# AUX_CurrentSource.net
KiCad netlist of a schematic drawn in Altium Designer
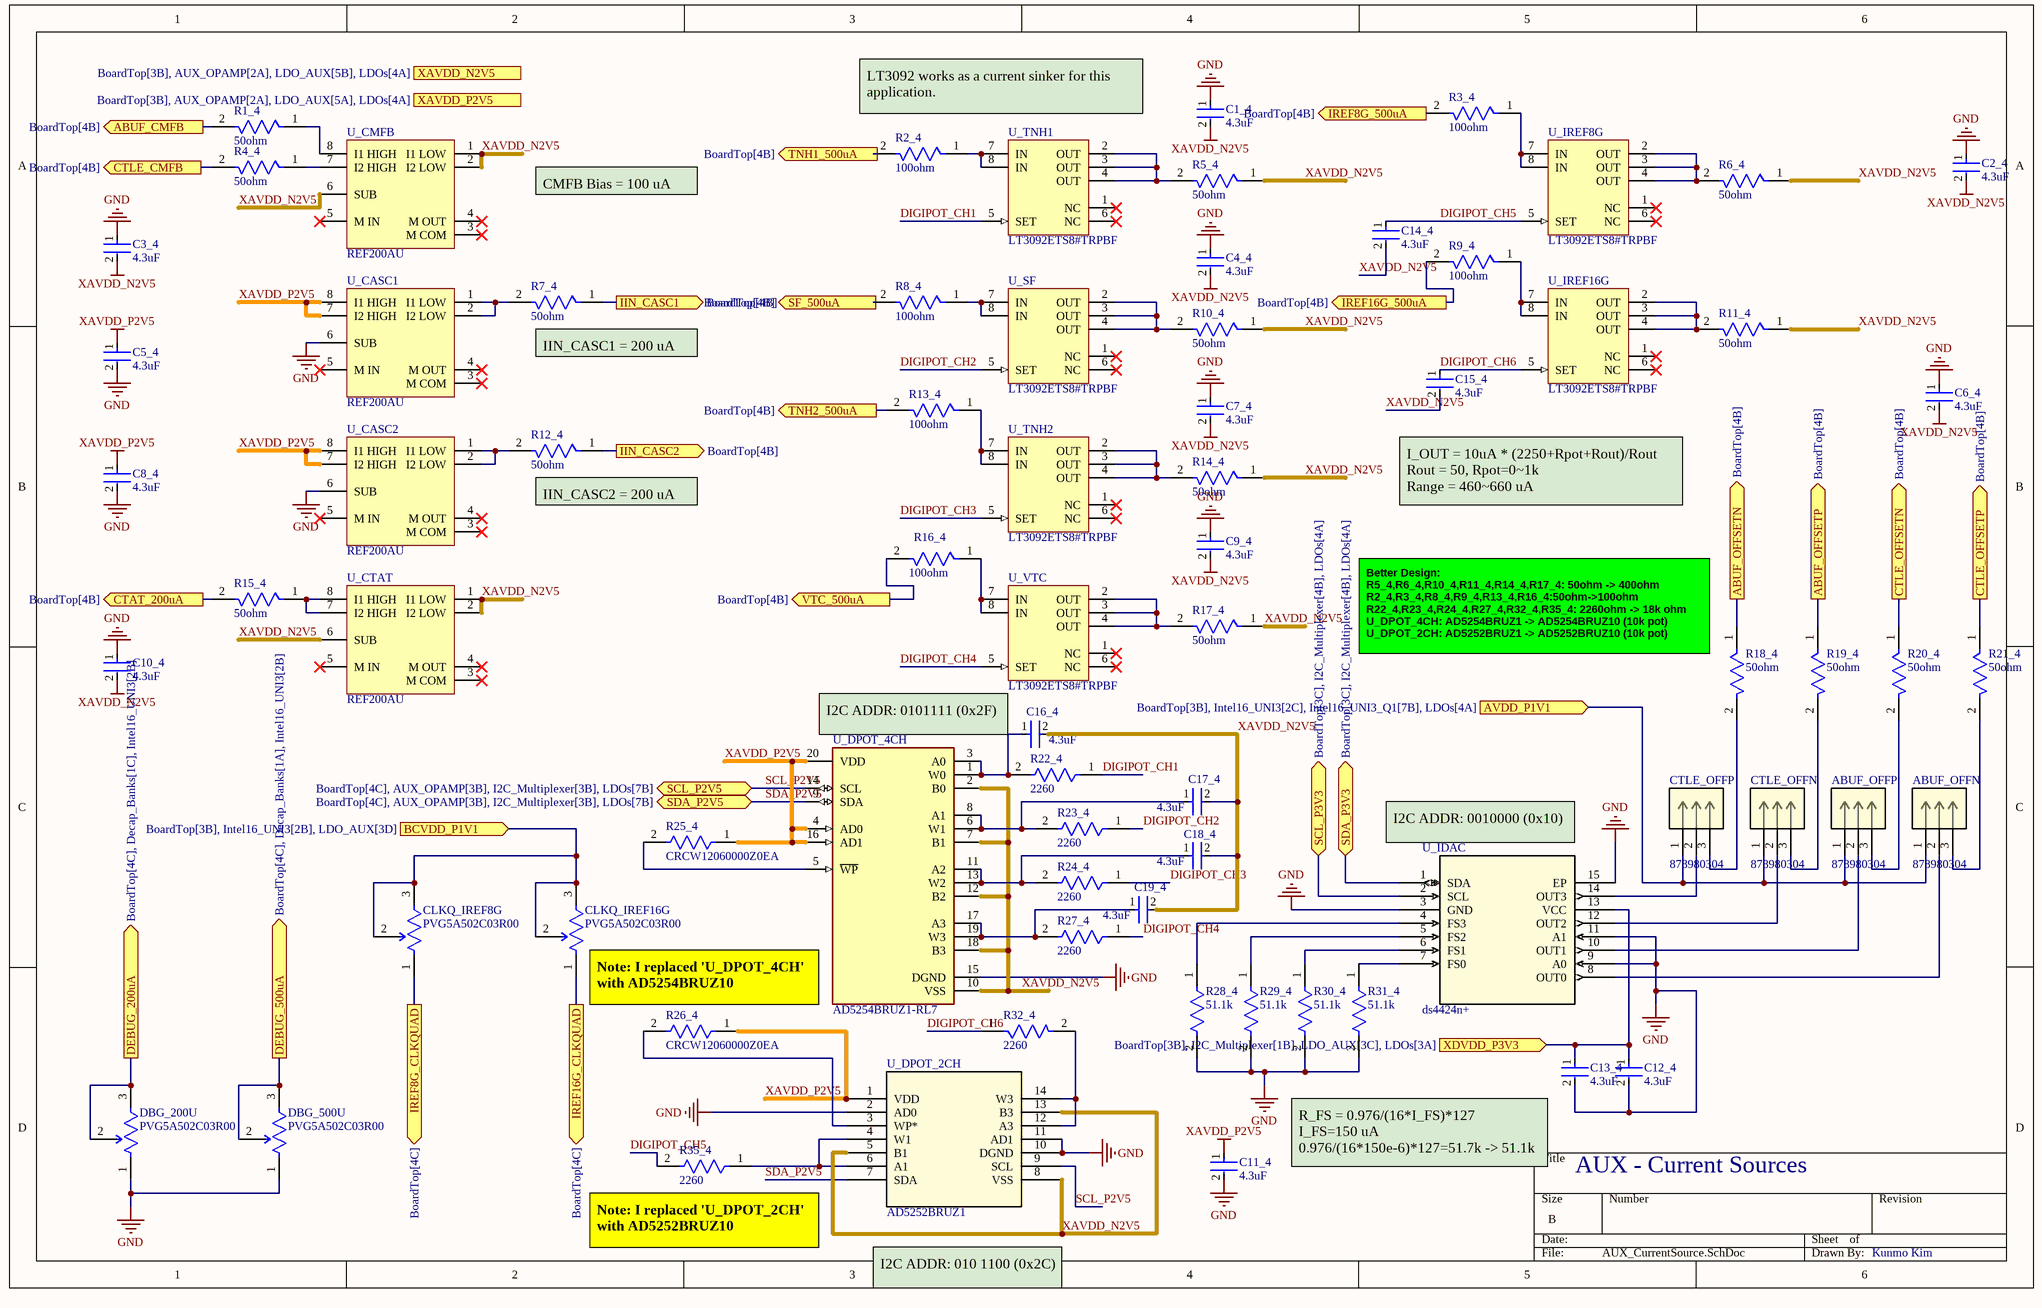
[diagram p0: AUX_CurrentSource.SchDoc]

(export (version "E")
  (design (tool "Eeschema 10.0.6"))
  (components
    (comp (ref "ABUF_OFFN")
      (value "878980304")
      (footprint "CONN03_87898_M-5p84_MOL")
      (description "No Description Available")
      (libsource (lib "878980304") (part "878980304"))
    )
    (comp (ref "ABUF_OFFP")
      (value "878980304")
      (footprint "CONN03_87898_M-5p84_MOL")
      (description "No Description Available")
      (libsource (lib "878980304") (part "878980304"))
    )
    (comp (ref "C1_4")
      (value "4.3uF")
      (footprint "FP-LLL1U4-0_05-MFG")
      (description "Cap Ceramic Monolithic 4.3uF 20% 4V X5R 15% 02404 (0610M)")
      (fields (field (name "TOLERANCE") "20%"))
      (libsource (lib "LLL_cap") (part "CMP-06035-061933-1"))
    )
    (comp (ref "C2_4")
      (value "4.3uF")
      (footprint "FP-LLL1U4-0_05-MFG")
      (description "Cap Ceramic Monolithic 4.3uF 20% 4V X5R 15% 02404 (0610M)")
      (fields (field (name "TOLERANCE") "20%"))
      (libsource (lib "LLL_cap") (part "CMP-06035-061933-1"))
    )
    (comp (ref "C3_4")
      (value "4.3uF")
      (footprint "FP-LLL1U4-0_05-MFG")
      (description "Cap Ceramic Monolithic 4.3uF 20% 4V X5R 15% 02404 (0610M)")
      (fields (field (name "TOLERANCE") "20%"))
      (libsource (lib "LLL_cap") (part "CMP-06035-061933-1"))
    )
    (comp (ref "C4_4")
      (value "4.3uF")
      (footprint "FP-LLL1U4-0_05-MFG")
      (description "Cap Ceramic Monolithic 4.3uF 20% 4V X5R 15% 02404 (0610M)")
      (fields (field (name "TOLERANCE") "20%"))
      (libsource (lib "LLL_cap") (part "CMP-06035-061933-1"))
    )
    (comp (ref "C5_4")
      (value "4.3uF")
      (footprint "FP-LLL1U4-0_05-MFG")
      (description "Cap Ceramic Monolithic 4.3uF 20% 4V X5R 15% 02404 (0610M)")
      (fields (field (name "TOLERANCE") "20%"))
      (libsource (lib "LLL_cap") (part "CMP-06035-061933-1"))
    )
    (comp (ref "C6_4")
      (value "4.3uF")
      (footprint "FP-LLL1U4-0_05-MFG")
      (description "Cap Ceramic Monolithic 4.3uF 20% 4V X5R 15% 02404 (0610M)")
      (fields (field (name "TOLERANCE") "20%"))
      (libsource (lib "LLL_cap") (part "CMP-06035-061933-1"))
    )
    (comp (ref "C7_4")
      (value "4.3uF")
      (footprint "FP-LLL1U4-0_05-MFG")
      (description "Cap Ceramic Monolithic 4.3uF 20% 4V X5R 15% 02404 (0610M)")
      (fields (field (name "TOLERANCE") "20%"))
      (libsource (lib "LLL_cap") (part "CMP-06035-061933-1"))
    )
    (comp (ref "C8_4")
      (value "4.3uF")
      (footprint "FP-LLL1U4-0_05-MFG")
      (description "Cap Ceramic Monolithic 4.3uF 20% 4V X5R 15% 02404 (0610M)")
      (fields (field (name "TOLERANCE") "20%"))
      (libsource (lib "LLL_cap") (part "CMP-06035-061933-1"))
    )
    (comp (ref "C9_4")
      (value "4.3uF")
      (footprint "FP-LLL1U4-0_05-MFG")
      (description "Cap Ceramic Monolithic 4.3uF 20% 4V X5R 15% 02404 (0610M)")
      (fields (field (name "TOLERANCE") "20%"))
      (libsource (lib "LLL_cap") (part "CMP-06035-061933-1"))
    )
    (comp (ref "C10_4")
      (value "4.3uF")
      (footprint "FP-LLL1U4-0_05-MFG")
      (description "Cap Ceramic Monolithic 4.3uF 20% 4V X5R 15% 02404 (0610M)")
      (fields (field (name "TOLERANCE") "20%"))
      (libsource (lib "LLL_cap") (part "CMP-06035-061933-1"))
    )
    (comp (ref "C11_4")
      (value "4.3uF")
      (footprint "FP-LLL1U4-0_05-MFG")
      (description "Cap Ceramic Monolithic 4.3uF 20% 4V X5R 15% 02404 (0610M)")
      (fields (field (name "TOLERANCE") "20%"))
      (libsource (lib "LLL_cap") (part "CMP-06035-061933-1"))
    )
    (comp (ref "C12_4")
      (value "4.3uF")
      (footprint "FP-LLL1U4-0_05-MFG")
      (description "Cap Ceramic Monolithic 4.3uF 20% 4V X5R 15% 02404 (0610M)")
      (fields (field (name "TOLERANCE") "20%"))
      (libsource (lib "LLL_cap") (part "CMP-06035-061933-1"))
    )
    (comp (ref "C13_4")
      (value "4.3uF")
      (footprint "FP-LLL1U4-0_05-MFG")
      (description "Cap Ceramic Monolithic 4.3uF 20% 4V X5R 15% 02404 (0610M)")
      (fields (field (name "TOLERANCE") "20%"))
      (libsource (lib "LLL_cap") (part "CMP-06035-061933-1"))
    )
    (comp (ref "C14_4")
      (value "4.3uF")
      (footprint "FP-LLL1U4-0_05-MFG")
      (description "Cap Ceramic Monolithic 4.3uF 20% 4V X5R 15% 02404 (0610M)")
      (fields (field (name "TOLERANCE") "20%"))
      (libsource (lib "LLL_cap") (part "CMP-06035-061933-1"))
    )
    (comp (ref "C15_4")
      (value "4.3uF")
      (footprint "FP-LLL1U4-0_05-MFG")
      (description "Cap Ceramic Monolithic 4.3uF 20% 4V X5R 15% 02404 (0610M)")
      (fields (field (name "TOLERANCE") "20%"))
      (libsource (lib "LLL_cap") (part "CMP-06035-061933-1"))
    )
    (comp (ref "C16_4")
      (value "4.3uF")
      (footprint "FP-LLL1U4-0_05-MFG")
      (description "Cap Ceramic Monolithic 4.3uF 20% 4V X5R 15% 02404 (0610M)")
      (fields (field (name "TOLERANCE") "20%"))
      (libsource (lib "LLL_cap") (part "CMP-06035-061933-1"))
    )
    (comp (ref "C17_4")
      (value "4.3uF")
      (footprint "FP-LLL1U4-0_05-MFG")
      (description "Cap Ceramic Monolithic 4.3uF 20% 4V X5R 15% 02404 (0610M)")
      (fields (field (name "TOLERANCE") "20%"))
      (libsource (lib "LLL_cap") (part "CMP-06035-061933-1"))
    )
    (comp (ref "C18_4")
      (value "4.3uF")
      (footprint "FP-LLL1U4-0_05-MFG")
      (description "Cap Ceramic Monolithic 4.3uF 20% 4V X5R 15% 02404 (0610M)")
      (fields (field (name "TOLERANCE") "20%"))
      (libsource (lib "LLL_cap") (part "CMP-06035-061933-1"))
    )
    (comp (ref "C19_4")
      (value "4.3uF")
      (footprint "FP-LLL1U4-0_05-MFG")
      (description "Cap Ceramic Monolithic 4.3uF 20% 4V X5R 15% 02404 (0610M)")
      (fields (field (name "TOLERANCE") "20%"))
      (libsource (lib "LLL_cap") (part "CMP-06035-061933-1"))
    )
    (comp (ref "CLKQ_IREF8G")
      (value "PVG5A502C03R00")
      (footprint "FP-PVG5A-MFG")
      (description "PVG5A502C03R00 Resistor Trimmer, Cermet, 5 kOhm, ± 10%, 250 mW, 12 Turn, Multi Turn, Surface Mount")
      (fields (field (name "TOLERANCE") "10%"))
      (libsource (lib "PVG5A502C03R00") (part "CMP-00059-71526922-1"))
    )
    (comp (ref "CLKQ_IREF16G")
      (value "PVG5A502C03R00")
      (footprint "FP-PVG5A-MFG")
      (description "PVG5A502C03R00 Resistor Trimmer, Cermet, 5 kOhm, ± 10%, 250 mW, 12 Turn, Multi Turn, Surface Mount")
      (fields (field (name "TOLERANCE") "10%"))
      (libsource (lib "PVG5A502C03R00") (part "CMP-00059-71526922-1"))
    )
    (comp (ref "CTLE_OFFN")
      (value "878980304")
      (footprint "CONN03_87898_M-5p84_MOL")
      (description "No Description Available")
      (libsource (lib "878980304") (part "878980304"))
    )
    (comp (ref "CTLE_OFFP")
      (value "878980304")
      (footprint "CONN03_87898_M-5p84_MOL")
      (description "No Description Available")
      (libsource (lib "878980304") (part "878980304"))
    )
    (comp (ref "DBG_200U")
      (value "PVG5A502C03R00")
      (footprint "FP-PVG5A-MFG")
      (description "PVG5A502C03R00 Resistor Trimmer, Cermet, 5 kOhm, ± 10%, 250 mW, 12 Turn, Multi Turn, Surface Mount")
      (fields (field (name "TOLERANCE") "10%"))
      (libsource (lib "PVG5A502C03R00") (part "CMP-00059-71526922-1"))
    )
    (comp (ref "DBG_500U")
      (value "PVG5A502C03R00")
      (footprint "FP-PVG5A-MFG")
      (description "PVG5A502C03R00 Resistor Trimmer, Cermet, 5 kOhm, ± 10%, 250 mW, 12 Turn, Multi Turn, Surface Mount")
      (fields (field (name "TOLERANCE") "10%"))
      (libsource (lib "PVG5A502C03R00") (part "CMP-00059-71526922-1"))
    )
    (comp (ref "R1_4")
      (value "50ohm")
      (footprint "FP-RT0402-0_35-IPC_A")
      (fields (field (name "TOLERANCE") "0.1%"))
      (libsource (lib "resistor_50ohm_0402_0p1ptol") (part "1029c3af85768c4190bb7ad29bc67b5"))
    )
    (comp (ref "R2_4")
      (value "100ohm")
      (footprint "FP-RT0402-0_35-IPC_A")
      (fields (field (name "TOLERANCE") "0.1%"))
      (libsource (lib "resistor_50ohm_0402_0p1ptol") (part "1029c3af85768c4190bb7ad29bc67b5"))
    )
    (comp (ref "R3_4")
      (value "100ohm")
      (footprint "FP-RT0402-0_35-IPC_A")
      (fields (field (name "TOLERANCE") "0.1%"))
      (libsource (lib "resistor_50ohm_0402_0p1ptol") (part "1029c3af85768c4190bb7ad29bc67b5"))
    )
    (comp (ref "R4_4")
      (value "50ohm")
      (footprint "FP-RT0402-0_35-IPC_A")
      (fields (field (name "TOLERANCE") "0.1%"))
      (libsource (lib "resistor_50ohm_0402_0p1ptol") (part "1029c3af85768c4190bb7ad29bc67b5"))
    )
    (comp (ref "R5_4")
      (value "50ohm")
      (footprint "FP-RT0402-0_35-IPC_A")
      (fields (field (name "TOLERANCE") "0.1%"))
      (libsource (lib "resistor_50ohm_0402_0p1ptol") (part "1029c3af85768c4190bb7ad29bc67b5"))
    )
    (comp (ref "R6_4")
      (value "50ohm")
      (footprint "FP-RT0402-0_35-IPC_A")
      (fields (field (name "TOLERANCE") "0.1%"))
      (libsource (lib "resistor_50ohm_0402_0p1ptol") (part "1029c3af85768c4190bb7ad29bc67b5"))
    )
    (comp (ref "R7_4")
      (value "50ohm")
      (footprint "FP-RT0402-0_35-IPC_A")
      (fields (field (name "TOLERANCE") "0.1%"))
      (libsource (lib "resistor_50ohm_0402_0p1ptol") (part "1029c3af85768c4190bb7ad29bc67b5"))
    )
    (comp (ref "R8_4")
      (value "100ohm")
      (footprint "FP-RT0402-0_35-IPC_A")
      (fields (field (name "TOLERANCE") "0.1%"))
      (libsource (lib "resistor_50ohm_0402_0p1ptol") (part "1029c3af85768c4190bb7ad29bc67b5"))
    )
    (comp (ref "R9_4")
      (value "100ohm")
      (footprint "FP-RT0402-0_35-IPC_A")
      (fields (field (name "TOLERANCE") "0.1%"))
      (libsource (lib "resistor_50ohm_0402_0p1ptol") (part "1029c3af85768c4190bb7ad29bc67b5"))
    )
    (comp (ref "R10_4")
      (value "50ohm")
      (footprint "FP-RT0402-0_35-IPC_A")
      (fields (field (name "TOLERANCE") "0.1%"))
      (libsource (lib "resistor_50ohm_0402_0p1ptol") (part "1029c3af85768c4190bb7ad29bc67b5"))
    )
    (comp (ref "R11_4")
      (value "50ohm")
      (footprint "FP-RT0402-0_35-IPC_A")
      (fields (field (name "TOLERANCE") "0.1%"))
      (libsource (lib "resistor_50ohm_0402_0p1ptol") (part "1029c3af85768c4190bb7ad29bc67b5"))
    )
    (comp (ref "R12_4")
      (value "50ohm")
      (footprint "FP-RT0402-0_35-IPC_A")
      (fields (field (name "TOLERANCE") "0.1%"))
      (libsource (lib "resistor_50ohm_0402_0p1ptol") (part "1029c3af85768c4190bb7ad29bc67b5"))
    )
    (comp (ref "R13_4")
      (value "100ohm")
      (footprint "FP-RT0402-0_35-IPC_A")
      (fields (field (name "TOLERANCE") "0.1%"))
      (libsource (lib "resistor_50ohm_0402_0p1ptol") (part "1029c3af85768c4190bb7ad29bc67b5"))
    )
    (comp (ref "R14_4")
      (value "50ohm")
      (footprint "FP-RT0402-0_35-IPC_A")
      (fields (field (name "TOLERANCE") "0.1%"))
      (libsource (lib "resistor_50ohm_0402_0p1ptol") (part "1029c3af85768c4190bb7ad29bc67b5"))
    )
    (comp (ref "R15_4")
      (value "50ohm")
      (footprint "FP-RT0402-0_35-IPC_A")
      (fields (field (name "TOLERANCE") "0.1%"))
      (libsource (lib "resistor_50ohm_0402_0p1ptol") (part "1029c3af85768c4190bb7ad29bc67b5"))
    )
    (comp (ref "R16_4")
      (value "100ohm")
      (footprint "FP-RT0402-0_35-IPC_A")
      (fields (field (name "TOLERANCE") "0.1%"))
      (libsource (lib "resistor_50ohm_0402_0p1ptol") (part "1029c3af85768c4190bb7ad29bc67b5"))
    )
    (comp (ref "R17_4")
      (value "50ohm")
      (footprint "FP-RT0402-0_35-IPC_A")
      (fields (field (name "TOLERANCE") "0.1%"))
      (libsource (lib "resistor_50ohm_0402_0p1ptol") (part "1029c3af85768c4190bb7ad29bc67b5"))
    )
    (comp (ref "R18_4")
      (value "50ohm")
      (footprint "FP-RT0402-0_35-IPC_A")
      (fields (field (name "TOLERANCE") "0.1%"))
      (libsource (lib "resistor_50ohm_0402_0p1ptol") (part "1029c3af85768c4190bb7ad29bc67b5"))
    )
    (comp (ref "R19_4")
      (value "50ohm")
      (footprint "FP-RT0402-0_35-IPC_A")
      (fields (field (name "TOLERANCE") "0.1%"))
      (libsource (lib "resistor_50ohm_0402_0p1ptol") (part "1029c3af85768c4190bb7ad29bc67b5"))
    )
    (comp (ref "R20_4")
      (value "50ohm")
      (footprint "FP-RT0402-0_35-IPC_A")
      (fields (field (name "TOLERANCE") "0.1%"))
      (libsource (lib "resistor_50ohm_0402_0p1ptol") (part "1029c3af85768c4190bb7ad29bc67b5"))
    )
    (comp (ref "R21_4")
      (value "50ohm")
      (footprint "FP-RT0402-0_35-IPC_A")
      (fields (field (name "TOLERANCE") "0.1%"))
      (libsource (lib "resistor_50ohm_0402_0p1ptol") (part "1029c3af85768c4190bb7ad29bc67b5"))
    )
    (comp (ref "R22_4")
      (value "2260")
      (footprint "FP-RG1005-MFG")
      (description "Automotive Metal Thin Film Chip Resistor, 0402, 2.26kΩ, 0.1%, 25ppm/°C, 0.0625W, 75V")
      (fields (field (name "TOLERANCE") "0.1%"))
      (libsource (lib "Altium Content Vault") (part "1029c3af85768c4190bb7ad29bc67b5"))
    )
    (comp (ref "R23_4")
      (value "2260")
      (footprint "FP-RG1005-MFG")
      (description "Automotive Metal Thin Film Chip Resistor, 0402, 2.26kΩ, 0.1%, 25ppm/°C, 0.0625W, 75V")
      (fields (field (name "TOLERANCE") "0.1%"))
      (libsource (lib "Altium Content Vault") (part "1029c3af85768c4190bb7ad29bc67b5"))
    )
    (comp (ref "R24_4")
      (value "2260")
      (footprint "FP-RG1005-MFG")
      (description "Automotive Metal Thin Film Chip Resistor, 0402, 2.26kΩ, 0.1%, 25ppm/°C, 0.0625W, 75V")
      (fields (field (name "TOLERANCE") "0.1%"))
      (libsource (lib "Altium Content Vault") (part "1029c3af85768c4190bb7ad29bc67b5"))
    )
    (comp (ref "R25_4")
      (value "CRCW12060000Z0EA")
      (footprint "FP-CRCW1206-e3-IPC_C")
      (description "RES Thick Film, 0Ω, 0.25W, 1206")
      (fields (field (name "TOLERANCE") "1%"))
      (libsource (lib "Altium Content Vault") (part "1029c3af85768c4190bb7ad29bc67b5"))
    )
    (comp (ref "R26_4")
      (value "CRCW12060000Z0EA")
      (footprint "FP-CRCW1206-e3-IPC_C")
      (description "RES Thick Film, 0Ω, 0.25W, 1206")
      (fields (field (name "TOLERANCE") "1%"))
      (libsource (lib "Altium Content Vault") (part "1029c3af85768c4190bb7ad29bc67b5"))
    )
    (comp (ref "R27_4")
      (value "2260")
      (footprint "FP-RG1005-MFG")
      (description "Automotive Metal Thin Film Chip Resistor, 0402, 2.26kΩ, 0.1%, 25ppm/°C, 0.0625W, 75V")
      (fields (field (name "TOLERANCE") "0.1%"))
      (libsource (lib "Altium Content Vault") (part "1029c3af85768c4190bb7ad29bc67b5"))
    )
    (comp (ref "R28_4")
      (value "51.1k")
      (footprint "FP-RT0603-MFG")
      (description "RES SMD 51.1K OHM 0.1% 1/10W")
      (fields (field (name "MANUFACTURER") "Yageo") (field (name "TOLERANCE") "0.001"))
      (libsource (lib "Altium Content Vault") (part "1029c3af85768c4190bb7ad29bc67b5"))
    )
    (comp (ref "R29_4")
      (value "51.1k")
      (footprint "FP-RT0603-MFG")
      (description "RES SMD 51.1K OHM 0.1% 1/10W")
      (fields (field (name "MANUFACTURER") "Yageo") (field (name "TOLERANCE") "0.001"))
      (libsource (lib "Altium Content Vault") (part "1029c3af85768c4190bb7ad29bc67b5"))
    )
    (comp (ref "R30_4")
      (value "51.1k")
      (footprint "FP-RT0603-MFG")
      (description "RES SMD 51.1K OHM 0.1% 1/10W")
      (fields (field (name "MANUFACTURER") "Yageo") (field (name "TOLERANCE") "0.001"))
      (libsource (lib "Altium Content Vault") (part "1029c3af85768c4190bb7ad29bc67b5"))
    )
    (comp (ref "R31_4")
      (value "51.1k")
      (footprint "FP-RT0603-MFG")
      (description "RES SMD 51.1K OHM 0.1% 1/10W")
      (fields (field (name "MANUFACTURER") "Yageo") (field (name "TOLERANCE") "0.001"))
      (libsource (lib "Altium Content Vault") (part "1029c3af85768c4190bb7ad29bc67b5"))
    )
    (comp (ref "R32_4")
      (value "2260")
      (footprint "FP-RG1005-MFG")
      (description "Automotive Metal Thin Film Chip Resistor, 0402, 2.26kΩ, 0.1%, 25ppm/°C, 0.0625W, 75V")
      (fields (field (name "TOLERANCE") "0.1%"))
      (libsource (lib "Altium Content Vault") (part "1029c3af85768c4190bb7ad29bc67b5"))
    )
    (comp (ref "R35_4")
      (value "2260")
      (footprint "FP-RG1005-MFG")
      (description "Automotive Metal Thin Film Chip Resistor, 0402, 2.26kΩ, 0.1%, 25ppm/°C, 0.0625W, 75V")
      (fields (field (name "TOLERANCE") "0.1%"))
      (libsource (lib "Altium Content Vault") (part "1029c3af85768c4190bb7ad29bc67b5"))
    )
    (comp (ref "U_CASC1")
      (value "REF200AU")
      (footprint "D0008A_N")
      (fields (field (name "MANUFACTURER") "Texas Instruments"))
      (libsource (lib "REF200") (part "CMP-0368-00004-2"))
    )
    (comp (ref "U_CASC2")
      (value "REF200AU")
      (footprint "D0008A_N")
      (fields (field (name "MANUFACTURER") "Texas Instruments"))
      (libsource (lib "REF200") (part "CMP-0368-00004-2"))
    )
    (comp (ref "U_CMFB")
      (value "REF200AU")
      (footprint "D0008A_N")
      (fields (field (name "MANUFACTURER") "Texas Instruments"))
      (libsource (lib "REF200") (part "CMP-0368-00004-2"))
    )
    (comp (ref "U_CTAT")
      (value "REF200AU")
      (footprint "D0008A_N")
      (fields (field (name "MANUFACTURER") "Texas Instruments"))
      (libsource (lib "REF200") (part "CMP-0368-00004-2"))
    )
    (comp (ref "U_DPOT_2CH")
      (value "AD5252BRUZ1")
      (footprint "RU_14_ADI")
      (description "No Description Available")
      (libsource (lib "AD5252BRUZ1") (part "AD5252BRUZ1"))
    )
    (comp (ref "U_DPOT_4CH")
      (value "AD5254BRUZ1-RL7")
      (footprint "FP-RU-20-IPC_B")
      (description "IC DGTL POT 1KOHM 256TAP 20TSSOP")
      (fields (field (name "TOLERANCE") "30%"))
      (libsource (lib "AD5254_1k") (part "CMP-09083-000143-1"))
    )
    (comp (ref "U_IDAC")
      (value "ds4424n+")
      (footprint "21-0137_T1433+2_MXM")
      (description "No Description Available")
      (libsource (lib "ds4424n&plus_") (part "ds4424n+"))
    )
    (comp (ref "U_IREF8G")
      (value "LT3092ETS8#TRPBF")
      (footprint "TSOT-23_TS8")
      (fields (field (name "MANUFACTURER") "Linear Technology"))
      (libsource (lib "LT3092") (part "CMP-0472-00072-1"))
    )
    (comp (ref "U_IREF16G")
      (value "LT3092ETS8#TRPBF")
      (footprint "TSOT-23_TS8")
      (fields (field (name "MANUFACTURER") "Linear Technology"))
      (libsource (lib "LT3092") (part "CMP-0472-00072-1"))
    )
    (comp (ref "U_SF")
      (value "LT3092ETS8#TRPBF")
      (footprint "TSOT-23_TS8")
      (fields (field (name "MANUFACTURER") "Linear Technology"))
      (libsource (lib "LT3092") (part "CMP-0472-00072-1"))
    )
    (comp (ref "U_TNH1")
      (value "LT3092ETS8#TRPBF")
      (footprint "TSOT-23_TS8")
      (fields (field (name "MANUFACTURER") "Linear Technology"))
      (libsource (lib "LT3092") (part "CMP-0472-00072-1"))
    )
    (comp (ref "U_TNH2")
      (value "LT3092ETS8#TRPBF")
      (footprint "TSOT-23_TS8")
      (fields (field (name "MANUFACTURER") "Linear Technology"))
      (libsource (lib "LT3092") (part "CMP-0472-00072-1"))
    )
    (comp (ref "U_VTC")
      (value "LT3092ETS8#TRPBF")
      (footprint "TSOT-23_TS8")
      (fields (field (name "MANUFACTURER") "Linear Technology"))
      (libsource (lib "LT3092") (part "CMP-0472-00072-1"))
    )
  )
  (nets
    (net (code "2") (name "/ABUF_CMFB") (class "Default")
      (node (ref "R1_4") (pin "2") (pinfunction "2_2") (pintype "passive"))
    )
    (net (code "3") (name "/ABUF_OFFSETN") (class "Default")
      (node (ref "R18_4") (pin "1") (pinfunction "1_1") (pintype "passive"))
    )
    (net (code "4") (name "/ABUF_OFFSETP") (class "Default")
      (node (ref "R19_4") (pin "1") (pinfunction "1_1") (pintype "passive"))
    )
    (net (code "5") (name "/AVDD_P1V1") (class "Default")
      (node (ref "ABUF_OFFN") (pin "1") (pinfunction "1_1") (pintype "passive"))
      (node (ref "ABUF_OFFP") (pin "1") (pinfunction "1_1") (pintype "passive"))
      (node (ref "CTLE_OFFN") (pin "1") (pinfunction "1_1") (pintype "passive"))
      (node (ref "CTLE_OFFP") (pin "1") (pinfunction "1_1") (pintype "passive"))
    )
    (net (code "6") (name "/BCVDD_P1V1") (class "Default")
      (node (ref "CLKQ_IREF16G") (pin "2") (pinfunction "WIPER_2") (pintype "passive"))
      (node (ref "CLKQ_IREF16G") (pin "3") (pinfunction "CW_3") (pintype "passive"))
      (node (ref "CLKQ_IREF8G") (pin "2") (pinfunction "WIPER_2") (pintype "passive"))
      (node (ref "CLKQ_IREF8G") (pin "3") (pinfunction "CW_3") (pintype "passive"))
    )
    (net (code "7") (name "/CTAT_200uA") (class "Default")
      (node (ref "R15_4") (pin "2") (pinfunction "2_2") (pintype "passive"))
    )
    (net (code "8") (name "/CTLE_CMFB") (class "Default")
      (node (ref "R4_4") (pin "2") (pinfunction "2_2") (pintype "passive"))
    )
    (net (code "9") (name "/CTLE_OFFSETN") (class "Default")
      (node (ref "R20_4") (pin "1") (pinfunction "1_1") (pintype "passive"))
    )
    (net (code "10") (name "/CTLE_OFFSETP") (class "Default")
      (node (ref "R21_4") (pin "1") (pinfunction "1_1") (pintype "passive"))
    )
    (net (code "11") (name "/DEBUG_200uA") (class "Default")
      (node (ref "DBG_200U") (pin "2") (pinfunction "WIPER_2") (pintype "passive"))
      (node (ref "DBG_200U") (pin "3") (pinfunction "CW_3") (pintype "passive"))
    )
    (net (code "12") (name "/DEBUG_500uA") (class "Default")
      (node (ref "DBG_500U") (pin "2") (pinfunction "WIPER_2") (pintype "passive"))
      (node (ref "DBG_500U") (pin "3") (pinfunction "CW_3") (pintype "passive"))
    )
    (net (code "13") (name "/DIGIPOT_CH1") (class "Default")
      (node (ref "R22_4") (pin "1") (pinfunction "1_1") (pintype "passive"))
      (node (ref "U_TNH1") (pin "5") (pinfunction "SET_5") (pintype "input"))
    )
    (net (code "14") (name "/DIGIPOT_CH2") (class "Default")
      (node (ref "R23_4") (pin "1") (pinfunction "1_1") (pintype "passive"))
      (node (ref "U_SF") (pin "5") (pinfunction "SET_5") (pintype "input"))
    )
    (net (code "15") (name "/DIGIPOT_CH3") (class "Default")
      (node (ref "R24_4") (pin "1") (pinfunction "1_1") (pintype "passive"))
      (node (ref "U_TNH2") (pin "5") (pinfunction "SET_5") (pintype "input"))
    )
    (net (code "16") (name "/DIGIPOT_CH4") (class "Default")
      (node (ref "R27_4") (pin "1") (pinfunction "1_1") (pintype "passive"))
      (node (ref "U_VTC") (pin "5") (pinfunction "SET_5") (pintype "input"))
    )
    (net (code "17") (name "/DIGIPOT_CH5") (class "Default")
      (node (ref "C14_4") (pin "1") (pinfunction "1_1") (pintype "passive"))
      (node (ref "R35_4") (pin "2") (pinfunction "2_2") (pintype "passive"))
      (node (ref "U_IREF8G") (pin "5") (pinfunction "SET_5") (pintype "input"))
    )
    (net (code "18") (name "/DIGIPOT_CH6") (class "Default")
      (node (ref "C15_4") (pin "1") (pinfunction "1_1") (pintype "passive"))
      (node (ref "R32_4") (pin "1") (pinfunction "1_1") (pintype "passive"))
      (node (ref "U_IREF16G") (pin "5") (pinfunction "SET_5") (pintype "input"))
    )
    (net (code "19") (name "/IIN_CASC1") (class "Default")
      (node (ref "R7_4") (pin "1") (pinfunction "1_1") (pintype "passive"))
    )
    (net (code "20") (name "/IIN_CASC2") (class "Default")
      (node (ref "R12_4") (pin "1") (pinfunction "1_1") (pintype "passive"))
    )
    (net (code "21") (name "/IREF8G_500uA") (class "Default")
      (node (ref "R3_4") (pin "2") (pinfunction "2_2") (pintype "passive"))
    )
    (net (code "22") (name "/IREF8G_CLKQUAD") (class "Default")
      (node (ref "CLKQ_IREF8G") (pin "1") (pinfunction "CCW_1") (pintype "passive"))
    )
    (net (code "23") (name "/IREF16G_500uA") (class "Default")
      (node (ref "R9_4") (pin "2") (pinfunction "2_2") (pintype "passive"))
    )
    (net (code "24") (name "/IREF16G_CLKQUAD") (class "Default")
      (node (ref "CLKQ_IREF16G") (pin "1") (pinfunction "CCW_1") (pintype "passive"))
    )
    (net (code "25") (name "/SCL_P2V5") (class "Default")
      (node (ref "U_DPOT_2CH") (pin "9") (pinfunction "SCL_9") (pintype "passive"))
      (node (ref "U_DPOT_4CH") (pin "14") (pinfunction "SCL_14") (pintype "bidirectional"))
    )
    (net (code "26") (name "/SCL_P3V3") (class "Default")
      (node (ref "U_IDAC") (pin "2") (pinfunction "SCL_2") (pintype "input"))
    )
    (net (code "27") (name "/SDA_P2V5") (class "Default")
      (node (ref "U_DPOT_2CH") (pin "7") (pinfunction "SDA_7") (pintype "passive"))
      (node (ref "U_DPOT_4CH") (pin "9") (pinfunction "SDA_9") (pintype "bidirectional"))
    )
    (net (code "28") (name "/SDA_P3V3") (class "Default")
      (node (ref "U_IDAC") (pin "1") (pinfunction "SDA_1") (pintype "bidirectional"))
    )
    (net (code "29") (name "/SF_500uA") (class "Default")
      (node (ref "R8_4") (pin "2") (pinfunction "2_2") (pintype "passive"))
    )
    (net (code "30") (name "/TNH1_500uA") (class "Default")
      (node (ref "R2_4") (pin "2") (pinfunction "2_2") (pintype "passive"))
    )
    (net (code "31") (name "/TNH2_500uA") (class "Default")
      (node (ref "R13_4") (pin "2") (pinfunction "2_2") (pintype "passive"))
    )
    (net (code "32") (name "/VTC_500uA") (class "Default")
      (node (ref "R16_4") (pin "2") (pinfunction "2_2") (pintype "passive"))
    )
    (net (code "33") (name "/XDVDD_P3V3") (class "Default")
      (node (ref "C12_4") (pin "1") (pinfunction "1_1") (pintype "passive"))
      (node (ref "C13_4") (pin "1") (pinfunction "1_1") (pintype "passive"))
      (node (ref "U_IDAC") (pin "13") (pinfunction "VCC_13") (pintype "power_in"))
    )
    (net (code "34") (name "GND") (class "Default")
      (node (ref "C10_4") (pin "1") (pinfunction "1_1") (pintype "passive"))
      (node (ref "C11_4") (pin "2") (pinfunction "2_2") (pintype "passive"))
      (node (ref "C12_4") (pin "2") (pinfunction "2_2") (pintype "passive"))
      (node (ref "C13_4") (pin "2") (pinfunction "2_2") (pintype "passive"))
      (node (ref "C1_4") (pin "1") (pinfunction "1_1") (pintype "passive"))
      (node (ref "C2_4") (pin "1") (pinfunction "1_1") (pintype "passive"))
      (node (ref "C3_4") (pin "1") (pinfunction "1_1") (pintype "passive"))
      (node (ref "C4_4") (pin "1") (pinfunction "1_1") (pintype "passive"))
      (node (ref "C5_4") (pin "2") (pinfunction "2_2") (pintype "passive"))
      (node (ref "C6_4") (pin "1") (pinfunction "1_1") (pintype "passive"))
      (node (ref "C7_4") (pin "1") (pinfunction "1_1") (pintype "passive"))
      (node (ref "C8_4") (pin "2") (pinfunction "2_2") (pintype "passive"))
      (node (ref "C9_4") (pin "1") (pinfunction "1_1") (pintype "passive"))
      (node (ref "DBG_200U") (pin "1") (pinfunction "CCW_1") (pintype "passive"))
      (node (ref "DBG_500U") (pin "1") (pinfunction "CCW_1") (pintype "passive"))
      (node (ref "R28_4") (pin "2") (pinfunction "2_2") (pintype "passive"))
      (node (ref "R29_4") (pin "2") (pinfunction "2_2") (pintype "passive"))
      (node (ref "R30_4") (pin "2") (pinfunction "2_2") (pintype "passive"))
      (node (ref "R31_4") (pin "2") (pinfunction "2_2") (pintype "passive"))
      (node (ref "U_CASC1") (pin "6") (pinfunction "SUB_6") (pintype "passive"))
      (node (ref "U_CASC2") (pin "6") (pinfunction "SUB_6") (pintype "passive"))
      (node (ref "U_DPOT_2CH") (pin "10") (pinfunction "DGND_10") (pintype "passive"))
      (node (ref "U_DPOT_2CH") (pin "11") (pinfunction "AD1_11") (pintype "passive"))
      (node (ref "U_DPOT_2CH") (pin "2") (pinfunction "AD0_2") (pintype "passive"))
      (node (ref "U_DPOT_4CH") (pin "15") (pinfunction "DGND_15") (pintype "power_in"))
      (node (ref "U_IDAC") (pin "11") (pinfunction "A1_11") (pintype "input"))
      (node (ref "U_IDAC") (pin "15") (pinfunction "EP_15") (pintype "passive"))
      (node (ref "U_IDAC") (pin "3") (pinfunction "GND_3") (pintype "power_in"))
      (node (ref "U_IDAC") (pin "9") (pinfunction "A0_9") (pintype "input"))
    )
    (net (code "35") (name "Net-(ABUF_OFFN-Pad3)") (class "Default")
      (node (ref "ABUF_OFFN") (pin "3") (pinfunction "3_3") (pintype "passive"))
      (node (ref "R21_4") (pin "2") (pinfunction "2_2") (pintype "passive"))
    )
    (net (code "36") (name "Net-(ABUF_OFFP-Pad3)") (class "Default")
      (node (ref "ABUF_OFFP") (pin "3") (pinfunction "3_3") (pintype "passive"))
      (node (ref "R20_4") (pin "2") (pinfunction "2_2") (pintype "passive"))
    )
    (net (code "37") (name "Net-(CTLE_OFFN-Pad3)") (class "Default")
      (node (ref "CTLE_OFFN") (pin "3") (pinfunction "3_3") (pintype "passive"))
      (node (ref "R19_4") (pin "2") (pinfunction "2_2") (pintype "passive"))
    )
    (net (code "38") (name "Net-(CTLE_OFFP-Pad3)") (class "Default")
      (node (ref "CTLE_OFFP") (pin "3") (pinfunction "3_3") (pintype "passive"))
      (node (ref "R18_4") (pin "2") (pinfunction "2_2") (pintype "passive"))
    )
    (net (code "39") (name "Net-(R2_4-Pad1)") (class "Default")
      (node (ref "R2_4") (pin "1") (pinfunction "1_1") (pintype "passive"))
      (node (ref "U_TNH1") (pin "7") (pinfunction "IN_7") (pintype "power_in"))
      (node (ref "U_TNH1") (pin "8") (pinfunction "IN_8") (pintype "power_in"))
    )
    (net (code "40") (name "Net-(R3_4-Pad1)") (class "Default")
      (node (ref "R3_4") (pin "1") (pinfunction "1_1") (pintype "passive"))
      (node (ref "U_IREF8G") (pin "7") (pinfunction "IN_7") (pintype "power_in"))
      (node (ref "U_IREF8G") (pin "8") (pinfunction "IN_8") (pintype "power_in"))
    )
    (net (code "41") (name "Net-(R5_4-Pad2)") (class "Default")
      (node (ref "R5_4") (pin "2") (pinfunction "2_2") (pintype "passive"))
      (node (ref "U_TNH1") (pin "2") (pinfunction "OUT_2") (pintype "power_in"))
      (node (ref "U_TNH1") (pin "3") (pinfunction "OUT_3") (pintype "power_in"))
      (node (ref "U_TNH1") (pin "4") (pinfunction "OUT_4") (pintype "power_in"))
    )
    (net (code "42") (name "Net-(R6_4-Pad2)") (class "Default")
      (node (ref "R6_4") (pin "2") (pinfunction "2_2") (pintype "passive"))
      (node (ref "U_IREF8G") (pin "2") (pinfunction "OUT_2") (pintype "power_in"))
      (node (ref "U_IREF8G") (pin "3") (pinfunction "OUT_3") (pintype "power_in"))
      (node (ref "U_IREF8G") (pin "4") (pinfunction "OUT_4") (pintype "power_in"))
    )
    (net (code "43") (name "Net-(R8_4-Pad1)") (class "Default")
      (node (ref "R8_4") (pin "1") (pinfunction "1_1") (pintype "passive"))
      (node (ref "U_SF") (pin "7") (pinfunction "IN_7") (pintype "power_in"))
      (node (ref "U_SF") (pin "8") (pinfunction "IN_8") (pintype "power_in"))
    )
    (net (code "44") (name "Net-(R9_4-Pad1)") (class "Default")
      (node (ref "R9_4") (pin "1") (pinfunction "1_1") (pintype "passive"))
      (node (ref "U_IREF16G") (pin "7") (pinfunction "IN_7") (pintype "power_in"))
      (node (ref "U_IREF16G") (pin "8") (pinfunction "IN_8") (pintype "power_in"))
    )
    (net (code "45") (name "Net-(R10_4-Pad2)") (class "Default")
      (node (ref "R10_4") (pin "2") (pinfunction "2_2") (pintype "passive"))
      (node (ref "U_SF") (pin "2") (pinfunction "OUT_2") (pintype "power_in"))
      (node (ref "U_SF") (pin "3") (pinfunction "OUT_3") (pintype "power_in"))
      (node (ref "U_SF") (pin "4") (pinfunction "OUT_4") (pintype "power_in"))
    )
    (net (code "46") (name "Net-(R11_4-Pad2)") (class "Default")
      (node (ref "R11_4") (pin "2") (pinfunction "2_2") (pintype "passive"))
      (node (ref "U_IREF16G") (pin "2") (pinfunction "OUT_2") (pintype "power_in"))
      (node (ref "U_IREF16G") (pin "3") (pinfunction "OUT_3") (pintype "power_in"))
      (node (ref "U_IREF16G") (pin "4") (pinfunction "OUT_4") (pintype "power_in"))
    )
    (net (code "47") (name "Net-(R13_4-Pad1)") (class "Default")
      (node (ref "R13_4") (pin "1") (pinfunction "1_1") (pintype "passive"))
      (node (ref "U_TNH2") (pin "7") (pinfunction "IN_7") (pintype "power_in"))
      (node (ref "U_TNH2") (pin "8") (pinfunction "IN_8") (pintype "power_in"))
    )
    (net (code "48") (name "Net-(R14_4-Pad2)") (class "Default")
      (node (ref "R14_4") (pin "2") (pinfunction "2_2") (pintype "passive"))
      (node (ref "U_TNH2") (pin "2") (pinfunction "OUT_2") (pintype "power_in"))
      (node (ref "U_TNH2") (pin "3") (pinfunction "OUT_3") (pintype "power_in"))
      (node (ref "U_TNH2") (pin "4") (pinfunction "OUT_4") (pintype "power_in"))
    )
    (net (code "49") (name "Net-(R16_4-Pad1)") (class "Default")
      (node (ref "R16_4") (pin "1") (pinfunction "1_1") (pintype "passive"))
      (node (ref "U_VTC") (pin "7") (pinfunction "IN_7") (pintype "power_in"))
      (node (ref "U_VTC") (pin "8") (pinfunction "IN_8") (pintype "power_in"))
    )
    (net (code "50") (name "Net-(R17_4-Pad2)") (class "Default")
      (node (ref "R17_4") (pin "2") (pinfunction "2_2") (pintype "passive"))
      (node (ref "U_VTC") (pin "2") (pinfunction "OUT_2") (pintype "power_in"))
      (node (ref "U_VTC") (pin "3") (pinfunction "OUT_3") (pintype "power_in"))
      (node (ref "U_VTC") (pin "4") (pinfunction "OUT_4") (pintype "power_in"))
    )
    (net (code "51") (name "Net-(U_CASC1-I1_LOW)") (class "Default")
      (node (ref "R7_4") (pin "2") (pinfunction "2_2") (pintype "passive"))
      (node (ref "U_CASC1") (pin "1") (pinfunction "I1_LOW_1") (pintype "passive"))
      (node (ref "U_CASC1") (pin "2") (pinfunction "I2_LOW_2") (pintype "passive"))
    )
    (net (code "52") (name "Net-(U_CASC2-I1_LOW)") (class "Default")
      (node (ref "R12_4") (pin "2") (pinfunction "2_2") (pintype "passive"))
      (node (ref "U_CASC2") (pin "1") (pinfunction "I1_LOW_1") (pintype "passive"))
      (node (ref "U_CASC2") (pin "2") (pinfunction "I2_LOW_2") (pintype "passive"))
    )
    (net (code "53") (name "Net-(U_CMFB-I1_HIGH)") (class "Default")
      (node (ref "R1_4") (pin "1") (pinfunction "1_1") (pintype "passive"))
      (node (ref "U_CMFB") (pin "8") (pinfunction "I1_HIGH_8") (pintype "passive"))
    )
    (net (code "54") (name "Net-(U_CMFB-I2_HIGH)") (class "Default")
      (node (ref "R4_4") (pin "1") (pinfunction "1_1") (pintype "passive"))
      (node (ref "U_CMFB") (pin "7") (pinfunction "I2_HIGH_7") (pintype "passive"))
    )
    (net (code "55") (name "Net-(U_CTAT-I1_HIGH)") (class "Default")
      (node (ref "R15_4") (pin "1") (pinfunction "1_1") (pintype "passive"))
      (node (ref "U_CTAT") (pin "7") (pinfunction "I2_HIGH_7") (pintype "passive"))
      (node (ref "U_CTAT") (pin "8") (pinfunction "I1_HIGH_8") (pintype "passive"))
    )
    (net (code "56") (name "Net-(U_DPOT_2CH-A1)") (class "Default")
      (node (ref "R35_4") (pin "1") (pinfunction "1_1") (pintype "passive"))
      (node (ref "U_DPOT_2CH") (pin "4") (pinfunction "W1_4") (pintype "passive"))
      (node (ref "U_DPOT_2CH") (pin "6") (pinfunction "A1_6") (pintype "passive"))
    )
    (net (code "57") (name "Net-(U_DPOT_2CH-A3)") (class "Default")
      (node (ref "R32_4") (pin "2") (pinfunction "2_2") (pintype "passive"))
      (node (ref "U_DPOT_2CH") (pin "12") (pinfunction "A3_12") (pintype "passive"))
      (node (ref "U_DPOT_2CH") (pin "14") (pinfunction "W3_14") (pintype "passive"))
    )
    (net (code "58") (name "Net-(U_DPOT_2CH-WP*)") (class "Default")
      (node (ref "R26_4") (pin "2") (pinfunction "2_2") (pintype "passive"))
      (node (ref "U_DPOT_2CH") (pin "3") (pinfunction "WP*_3") (pintype "passive"))
    )
    (net (code "59") (name "Net-(U_DPOT_4CH-A0)") (class "Default")
      (node (ref "C16_4") (pin "1") (pinfunction "1_1") (pintype "passive"))
      (node (ref "R22_4") (pin "2") (pinfunction "2_2") (pintype "passive"))
      (node (ref "U_DPOT_4CH") (pin "1") (pinfunction "W0_1") (pintype "passive"))
      (node (ref "U_DPOT_4CH") (pin "3") (pinfunction "A0_3") (pintype "passive"))
    )
    (net (code "60") (name "Net-(U_DPOT_4CH-A1)") (class "Default")
      (node (ref "C17_4") (pin "1") (pinfunction "1_1") (pintype "passive"))
      (node (ref "R23_4") (pin "2") (pinfunction "2_2") (pintype "passive"))
      (node (ref "U_DPOT_4CH") (pin "6") (pinfunction "W1_6") (pintype "passive"))
      (node (ref "U_DPOT_4CH") (pin "8") (pinfunction "A1_8") (pintype "passive"))
    )
    (net (code "61") (name "Net-(U_DPOT_4CH-A2)") (class "Default")
      (node (ref "C18_4") (pin "1") (pinfunction "1_1") (pintype "passive"))
      (node (ref "R24_4") (pin "2") (pinfunction "2_2") (pintype "passive"))
      (node (ref "U_DPOT_4CH") (pin "11") (pinfunction "A2_11") (pintype "passive"))
      (node (ref "U_DPOT_4CH") (pin "13") (pinfunction "W2_13") (pintype "passive"))
    )
    (net (code "62") (name "Net-(U_DPOT_4CH-A3)") (class "Default")
      (node (ref "C19_4") (pin "1") (pinfunction "1_1") (pintype "passive"))
      (node (ref "R27_4") (pin "2") (pinfunction "2_2") (pintype "passive"))
      (node (ref "U_DPOT_4CH") (pin "17") (pinfunction "A3_17") (pintype "passive"))
      (node (ref "U_DPOT_4CH") (pin "19") (pinfunction "W3_19") (pintype "passive"))
    )
    (net (code "63") (name "Net-(U_DPOT_4CH-~{WP})") (class "Default")
      (node (ref "R25_4") (pin "2") (pinfunction "2_2") (pintype "passive"))
      (node (ref "U_DPOT_4CH") (pin "5") (pinfunction "~{WP}_5") (pintype "input"))
    )
    (net (code "64") (name "Net-(U_IDAC-FS0)") (class "Default")
      (node (ref "R31_4") (pin "1") (pinfunction "1_1") (pintype "passive"))
      (node (ref "U_IDAC") (pin "7") (pinfunction "FS0_7") (pintype "input"))
    )
    (net (code "65") (name "Net-(U_IDAC-FS1)") (class "Default")
      (node (ref "R30_4") (pin "1") (pinfunction "1_1") (pintype "passive"))
      (node (ref "U_IDAC") (pin "6") (pinfunction "FS1_6") (pintype "input"))
    )
    (net (code "66") (name "Net-(U_IDAC-FS2)") (class "Default")
      (node (ref "R29_4") (pin "1") (pinfunction "1_1") (pintype "passive"))
      (node (ref "U_IDAC") (pin "5") (pinfunction "FS2_5") (pintype "input"))
    )
    (net (code "67") (name "Net-(U_IDAC-FS3)") (class "Default")
      (node (ref "R28_4") (pin "1") (pinfunction "1_1") (pintype "passive"))
      (node (ref "U_IDAC") (pin "4") (pinfunction "FS3_4") (pintype "input"))
    )
    (net (code "68") (name "Net-(U_IDAC-OUT0)") (class "Default")
      (node (ref "ABUF_OFFN") (pin "2") (pinfunction "2_2") (pintype "passive"))
      (node (ref "U_IDAC") (pin "8") (pinfunction "OUT0_8") (pintype "output"))
    )
    (net (code "69") (name "Net-(U_IDAC-OUT1)") (class "Default")
      (node (ref "ABUF_OFFP") (pin "2") (pinfunction "2_2") (pintype "passive"))
      (node (ref "U_IDAC") (pin "10") (pinfunction "OUT1_10") (pintype "output"))
    )
    (net (code "70") (name "Net-(U_IDAC-OUT2)") (class "Default")
      (node (ref "CTLE_OFFN") (pin "2") (pinfunction "2_2") (pintype "passive"))
      (node (ref "U_IDAC") (pin "12") (pinfunction "OUT2_12") (pintype "output"))
    )
    (net (code "71") (name "Net-(U_IDAC-OUT3)") (class "Default")
      (node (ref "CTLE_OFFP") (pin "2") (pinfunction "2_2") (pintype "passive"))
      (node (ref "U_IDAC") (pin "14") (pinfunction "OUT3_14") (pintype "output"))
    )
    (net (code "72") (name "XAVDD_N2V5") (class "Default")
      (node (ref "C10_4") (pin "2") (pinfunction "2_2") (pintype "passive"))
      (node (ref "C14_4") (pin "2") (pinfunction "2_2") (pintype "passive"))
      (node (ref "C15_4") (pin "2") (pinfunction "2_2") (pintype "passive"))
      (node (ref "C16_4") (pin "2") (pinfunction "2_2") (pintype "passive"))
      (node (ref "C17_4") (pin "2") (pinfunction "2_2") (pintype "passive"))
      (node (ref "C18_4") (pin "2") (pinfunction "2_2") (pintype "passive"))
      (node (ref "C19_4") (pin "2") (pinfunction "2_2") (pintype "passive"))
      (node (ref "C1_4") (pin "2") (pinfunction "2_2") (pintype "passive"))
      (node (ref "C2_4") (pin "2") (pinfunction "2_2") (pintype "passive"))
      (node (ref "C3_4") (pin "2") (pinfunction "2_2") (pintype "passive"))
      (node (ref "C4_4") (pin "2") (pinfunction "2_2") (pintype "passive"))
      (node (ref "C6_4") (pin "2") (pinfunction "2_2") (pintype "passive"))
      (node (ref "C7_4") (pin "2") (pinfunction "2_2") (pintype "passive"))
      (node (ref "C9_4") (pin "2") (pinfunction "2_2") (pintype "passive"))
      (node (ref "R10_4") (pin "1") (pinfunction "1_1") (pintype "passive"))
      (node (ref "R11_4") (pin "1") (pinfunction "1_1") (pintype "passive"))
      (node (ref "R14_4") (pin "1") (pinfunction "1_1") (pintype "passive"))
      (node (ref "R17_4") (pin "1") (pinfunction "1_1") (pintype "passive"))
      (node (ref "R5_4") (pin "1") (pinfunction "1_1") (pintype "passive"))
      (node (ref "R6_4") (pin "1") (pinfunction "1_1") (pintype "passive"))
      (node (ref "U_CMFB") (pin "1") (pinfunction "I1_LOW_1") (pintype "passive"))
      (node (ref "U_CMFB") (pin "2") (pinfunction "I2_LOW_2") (pintype "passive"))
      (node (ref "U_CMFB") (pin "6") (pinfunction "SUB_6") (pintype "passive"))
      (node (ref "U_CTAT") (pin "1") (pinfunction "I1_LOW_1") (pintype "passive"))
      (node (ref "U_CTAT") (pin "2") (pinfunction "I2_LOW_2") (pintype "passive"))
      (node (ref "U_CTAT") (pin "6") (pinfunction "SUB_6") (pintype "passive"))
      (node (ref "U_DPOT_2CH") (pin "13") (pinfunction "B3_13") (pintype "passive"))
      (node (ref "U_DPOT_2CH") (pin "5") (pinfunction "B1_5") (pintype "passive"))
      (node (ref "U_DPOT_2CH") (pin "8") (pinfunction "VSS_8") (pintype "power_in"))
      (node (ref "U_DPOT_4CH") (pin "10") (pinfunction "VSS_10") (pintype "power_in"))
      (node (ref "U_DPOT_4CH") (pin "12") (pinfunction "B2_12") (pintype "passive"))
      (node (ref "U_DPOT_4CH") (pin "18") (pinfunction "B3_18") (pintype "passive"))
      (node (ref "U_DPOT_4CH") (pin "2") (pinfunction "B0_2") (pintype "passive"))
      (node (ref "U_DPOT_4CH") (pin "7") (pinfunction "B1_7") (pintype "passive"))
    )
    (net (code "73") (name "XAVDD_P2V5") (class "Default")
      (node (ref "C11_4") (pin "1") (pinfunction "1_1") (pintype "passive"))
      (node (ref "C5_4") (pin "1") (pinfunction "1_1") (pintype "passive"))
      (node (ref "C8_4") (pin "1") (pinfunction "1_1") (pintype "passive"))
      (node (ref "R25_4") (pin "1") (pinfunction "1_1") (pintype "passive"))
      (node (ref "R26_4") (pin "1") (pinfunction "1_1") (pintype "passive"))
      (node (ref "U_CASC1") (pin "7") (pinfunction "I2_HIGH_7") (pintype "passive"))
      (node (ref "U_CASC1") (pin "8") (pinfunction "I1_HIGH_8") (pintype "passive"))
      (node (ref "U_CASC2") (pin "7") (pinfunction "I2_HIGH_7") (pintype "passive"))
      (node (ref "U_CASC2") (pin "8") (pinfunction "I1_HIGH_8") (pintype "passive"))
      (node (ref "U_DPOT_2CH") (pin "1") (pinfunction "VDD_1") (pintype "power_in"))
      (node (ref "U_DPOT_4CH") (pin "16") (pinfunction "AD1_16") (pintype "input"))
      (node (ref "U_DPOT_4CH") (pin "20") (pinfunction "VDD_20") (pintype "power_in"))
      (node (ref "U_DPOT_4CH") (pin "4") (pinfunction "AD0_4") (pintype "input"))
    )
    (net (code "74") (name "unconnected-(U_CASC1-M_COM-Pad3)") (class "Default")
      (node (ref "U_CASC1") (pin "3") (pinfunction "M_COM_3") (pintype "passive+no_connect"))
    )
    (net (code "75") (name "unconnected-(U_CASC1-M_IN-Pad5)") (class "Default")
      (node (ref "U_CASC1") (pin "5") (pinfunction "M_IN_5") (pintype "passive+no_connect"))
    )
    (net (code "76") (name "unconnected-(U_CASC1-M_OUT-Pad4)") (class "Default")
      (node (ref "U_CASC1") (pin "4") (pinfunction "M_OUT_4") (pintype "passive+no_connect"))
    )
    (net (code "77") (name "unconnected-(U_CASC2-M_COM-Pad3)") (class "Default")
      (node (ref "U_CASC2") (pin "3") (pinfunction "M_COM_3") (pintype "passive+no_connect"))
    )
    (net (code "78") (name "unconnected-(U_CASC2-M_IN-Pad5)") (class "Default")
      (node (ref "U_CASC2") (pin "5") (pinfunction "M_IN_5") (pintype "passive+no_connect"))
    )
    (net (code "79") (name "unconnected-(U_CASC2-M_OUT-Pad4)") (class "Default")
      (node (ref "U_CASC2") (pin "4") (pinfunction "M_OUT_4") (pintype "passive+no_connect"))
    )
    (net (code "80") (name "unconnected-(U_CMFB-M_COM-Pad3)") (class "Default")
      (node (ref "U_CMFB") (pin "3") (pinfunction "M_COM_3") (pintype "passive+no_connect"))
    )
    (net (code "81") (name "unconnected-(U_CMFB-M_IN-Pad5)") (class "Default")
      (node (ref "U_CMFB") (pin "5") (pinfunction "M_IN_5") (pintype "passive+no_connect"))
    )
    (net (code "82") (name "unconnected-(U_CMFB-M_OUT-Pad4)") (class "Default")
      (node (ref "U_CMFB") (pin "4") (pinfunction "M_OUT_4") (pintype "passive+no_connect"))
    )
    (net (code "83") (name "unconnected-(U_CTAT-M_COM-Pad3)") (class "Default")
      (node (ref "U_CTAT") (pin "3") (pinfunction "M_COM_3") (pintype "passive+no_connect"))
    )
    (net (code "84") (name "unconnected-(U_CTAT-M_IN-Pad5)") (class "Default")
      (node (ref "U_CTAT") (pin "5") (pinfunction "M_IN_5") (pintype "passive+no_connect"))
    )
    (net (code "85") (name "unconnected-(U_CTAT-M_OUT-Pad4)") (class "Default")
      (node (ref "U_CTAT") (pin "4") (pinfunction "M_OUT_4") (pintype "passive+no_connect"))
    )
    (net (code "86") (name "unconnected-(U_IREF8G-NC-Pad1)") (class "Default")
      (node (ref "U_IREF8G") (pin "1") (pinfunction "NC_1") (pintype "passive+no_connect"))
    )
    (net (code "87") (name "unconnected-(U_IREF8G-NC-Pad6)") (class "Default")
      (node (ref "U_IREF8G") (pin "6") (pinfunction "NC_6") (pintype "passive+no_connect"))
    )
    (net (code "88") (name "unconnected-(U_IREF16G-NC-Pad1)") (class "Default")
      (node (ref "U_IREF16G") (pin "1") (pinfunction "NC_1") (pintype "passive+no_connect"))
    )
    (net (code "89") (name "unconnected-(U_IREF16G-NC-Pad6)") (class "Default")
      (node (ref "U_IREF16G") (pin "6") (pinfunction "NC_6") (pintype "passive+no_connect"))
    )
    (net (code "90") (name "unconnected-(U_SF-NC-Pad1)") (class "Default")
      (node (ref "U_SF") (pin "1") (pinfunction "NC_1") (pintype "passive+no_connect"))
    )
    (net (code "91") (name "unconnected-(U_SF-NC-Pad6)") (class "Default")
      (node (ref "U_SF") (pin "6") (pinfunction "NC_6") (pintype "passive+no_connect"))
    )
    (net (code "92") (name "unconnected-(U_TNH1-NC-Pad1)") (class "Default")
      (node (ref "U_TNH1") (pin "1") (pinfunction "NC_1") (pintype "passive+no_connect"))
    )
    (net (code "93") (name "unconnected-(U_TNH1-NC-Pad6)") (class "Default")
      (node (ref "U_TNH1") (pin "6") (pinfunction "NC_6") (pintype "passive+no_connect"))
    )
    (net (code "94") (name "unconnected-(U_TNH2-NC-Pad1)") (class "Default")
      (node (ref "U_TNH2") (pin "1") (pinfunction "NC_1") (pintype "passive+no_connect"))
    )
    (net (code "95") (name "unconnected-(U_TNH2-NC-Pad6)") (class "Default")
      (node (ref "U_TNH2") (pin "6") (pinfunction "NC_6") (pintype "passive+no_connect"))
    )
    (net (code "96") (name "unconnected-(U_VTC-NC-Pad1)") (class "Default")
      (node (ref "U_VTC") (pin "1") (pinfunction "NC_1") (pintype "passive+no_connect"))
    )
    (net (code "97") (name "unconnected-(U_VTC-NC-Pad6)") (class "Default")
      (node (ref "U_VTC") (pin "6") (pinfunction "NC_6") (pintype "passive+no_connect"))
    )
  )
)
